# 05021002_7-Segment_Display.net
KiCad netlist of a schematic drawn in Altium Designer
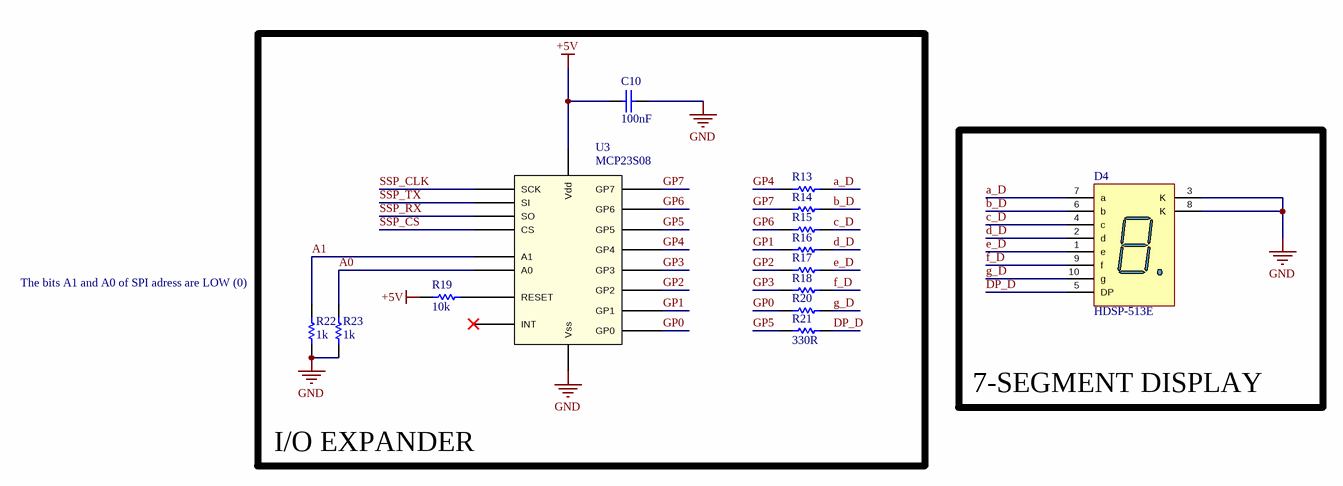
[diagram p0: 05021002_7-Segment Display.SchDoc]

(export (version "E")
  (design (tool "Eeschema 10.0.6"))
  (components
    (comp (ref "C10")
      (value "100nF")
      (footprint "CAPC2012X135N")
      (description "Generic Capacitor")
      (libsource (lib "capacitor_smd_gen") (part "capacitor_gen"))
    )
    (comp (ref "D4")
      (value "HDSP-513E")
      (footprint "HDSP-513E")
      (description "14.22 mm (0.56 inch) Single Digit General Purpose Seven Segment Display")
      (libsource (lib "IPÊ_BOARD_LIBRARY") (part "HDSP-513E"))
    )
    (comp (ref "R13")
      (value "330R")
      (footprint "0805")
      (libsource (lib "resistor_smd_gen") (part "resistor_gen"))
    )
    (comp (ref "R14")
      (value "330R")
      (footprint "0805")
      (libsource (lib "resistor_smd_gen") (part "resistor_gen"))
    )
    (comp (ref "R15")
      (value "330R")
      (footprint "0805")
      (libsource (lib "resistor_smd_gen") (part "resistor_gen"))
    )
    (comp (ref "R16")
      (value "330R")
      (footprint "0805")
      (libsource (lib "resistor_smd_gen") (part "resistor_gen"))
    )
    (comp (ref "R17")
      (value "330R")
      (footprint "0805")
      (libsource (lib "resistor_smd_gen") (part "resistor_gen"))
    )
    (comp (ref "R18")
      (value "330R")
      (footprint "0805")
      (libsource (lib "resistor_smd_gen") (part "resistor_gen"))
    )
    (comp (ref "R19")
      (value "10k")
      (footprint "0805")
      (libsource (lib "resistor_smd_gen") (part "resistor_gen"))
    )
    (comp (ref "R20")
      (value "330R")
      (footprint "0805")
      (libsource (lib "resistor_smd_gen") (part "resistor_gen"))
    )
    (comp (ref "R21")
      (value "330R")
      (footprint "0805")
      (libsource (lib "resistor_smd_gen") (part "resistor_gen"))
    )
    (comp (ref "R22")
      (value "1k")
      (footprint "0805")
      (libsource (lib "resistor_smd_gen") (part "resistor_gen"))
    )
    (comp (ref "R23")
      (value "1k")
      (footprint "0805")
      (libsource (lib "resistor_smd_gen") (part "resistor_gen"))
    )
    (comp (ref "U3")
      (value "MCP23S08")
      (footprint "SSOP20")
      (description "8-Bit I/O Expander with Serial Interface")
      (libsource (lib "IPÊ_BOARD_LIBRARY") (part "MCP23S08"))
    )
  )
  (nets
    (net (code "1") (name "+5V") (class "Default")
      (node (ref "C10") (pin "1") (pinfunction "1_1") (pintype "passive"))
      (node (ref "R19") (pin "2") (pinfunction "2_2") (pintype "passive"))
      (node (ref "U3") (pin "20") (pinfunction "Vdd_20") (pintype "passive"))
    )
    (net (code "2") (name "/A0") (class "Default")
      (node (ref "R23") (pin "2") (pinfunction "2_2") (pintype "passive"))
      (node (ref "U3") (pin "5") (pinfunction "A0_5") (pintype "passive"))
    )
    (net (code "3") (name "/A1") (class "Default")
      (node (ref "R22") (pin "2") (pinfunction "2_2") (pintype "passive"))
      (node (ref "U3") (pin "4") (pinfunction "A1_4") (pintype "passive"))
    )
    (net (code "4") (name "/DP_D") (class "Default")
      (node (ref "D4") (pin "5") (pinfunction "DP_5") (pintype "passive"))
      (node (ref "R21") (pin "2") (pinfunction "2_2") (pintype "passive"))
    )
    (net (code "5") (name "/GP0") (class "Default")
      (node (ref "R20") (pin "1") (pinfunction "1_1") (pintype "passive"))
      (node (ref "U3") (pin "12") (pinfunction "GP0_12") (pintype "passive"))
    )
    (net (code "6") (name "/GP1") (class "Default")
      (node (ref "R16") (pin "1") (pinfunction "1_1") (pintype "passive"))
      (node (ref "U3") (pin "13") (pinfunction "GP1_13") (pintype "passive"))
    )
    (net (code "7") (name "/GP2") (class "Default")
      (node (ref "R17") (pin "1") (pinfunction "1_1") (pintype "passive"))
      (node (ref "U3") (pin "14") (pinfunction "GP2_14") (pintype "passive"))
    )
    (net (code "8") (name "/GP3") (class "Default")
      (node (ref "R18") (pin "1") (pinfunction "1_1") (pintype "passive"))
      (node (ref "U3") (pin "15") (pinfunction "GP3_15") (pintype "passive"))
    )
    (net (code "9") (name "/GP4") (class "Default")
      (node (ref "R13") (pin "1") (pinfunction "1_1") (pintype "passive"))
      (node (ref "U3") (pin "16") (pinfunction "GP4_16") (pintype "passive"))
    )
    (net (code "10") (name "/GP5") (class "Default")
      (node (ref "R21") (pin "1") (pinfunction "1_1") (pintype "passive"))
      (node (ref "U3") (pin "17") (pinfunction "GP5_17") (pintype "passive"))
    )
    (net (code "11") (name "/GP6") (class "Default")
      (node (ref "R15") (pin "1") (pinfunction "1_1") (pintype "passive"))
      (node (ref "U3") (pin "18") (pinfunction "GP6_18") (pintype "passive"))
    )
    (net (code "12") (name "/GP7") (class "Default")
      (node (ref "R14") (pin "1") (pinfunction "1_1") (pintype "passive"))
      (node (ref "U3") (pin "19") (pinfunction "GP7_19") (pintype "passive"))
    )
    (net (code "13") (name "/SSP_CLK") (class "Default")
      (node (ref "U3") (pin "1") (pinfunction "SCK_1") (pintype "passive"))
    )
    (net (code "14") (name "/SSP_CS") (class "Default")
      (node (ref "U3") (pin "7") (pinfunction "CS_7") (pintype "passive"))
    )
    (net (code "15") (name "/SSP_RX") (class "Default")
      (node (ref "U3") (pin "3") (pinfunction "SO_3") (pintype "passive"))
    )
    (net (code "16") (name "/SSP_TX") (class "Default")
      (node (ref "U3") (pin "2") (pinfunction "SI_2") (pintype "passive"))
    )
    (net (code "17") (name "/a_D") (class "Default")
      (node (ref "D4") (pin "7") (pinfunction "a_7") (pintype "passive"))
      (node (ref "R13") (pin "2") (pinfunction "2_2") (pintype "passive"))
    )
    (net (code "18") (name "/b_D") (class "Default")
      (node (ref "D4") (pin "6") (pinfunction "b_6") (pintype "passive"))
      (node (ref "R14") (pin "2") (pinfunction "2_2") (pintype "passive"))
    )
    (net (code "19") (name "/c_D") (class "Default")
      (node (ref "D4") (pin "4") (pinfunction "c_4") (pintype "passive"))
      (node (ref "R15") (pin "2") (pinfunction "2_2") (pintype "passive"))
    )
    (net (code "20") (name "/d_D") (class "Default")
      (node (ref "D4") (pin "2") (pinfunction "d_2") (pintype "passive"))
      (node (ref "R16") (pin "2") (pinfunction "2_2") (pintype "passive"))
    )
    (net (code "21") (name "/e_D") (class "Default")
      (node (ref "D4") (pin "1") (pinfunction "e_1") (pintype "passive"))
      (node (ref "R17") (pin "2") (pinfunction "2_2") (pintype "passive"))
    )
    (net (code "22") (name "/f_D") (class "Default")
      (node (ref "D4") (pin "9") (pinfunction "f_9") (pintype "passive"))
      (node (ref "R18") (pin "2") (pinfunction "2_2") (pintype "passive"))
    )
    (net (code "23") (name "/g_D") (class "Default")
      (node (ref "D4") (pin "10") (pinfunction "g_10") (pintype "passive"))
      (node (ref "R20") (pin "2") (pinfunction "2_2") (pintype "passive"))
    )
    (net (code "24") (name "GND") (class "Default")
      (node (ref "C10") (pin "2") (pinfunction "2_2") (pintype "passive"))
      (node (ref "D4") (pin "3") (pinfunction "K_3") (pintype "passive"))
      (node (ref "D4") (pin "8") (pinfunction "K_8") (pintype "passive"))
      (node (ref "R22") (pin "1") (pinfunction "1_1") (pintype "passive"))
      (node (ref "R23") (pin "1") (pinfunction "1_1") (pintype "passive"))
      (node (ref "U3") (pin "9") (pinfunction "Vss_9") (pintype "passive"))
    )
    (net (code "25") (name "Net-(U3-RESET)") (class "Default")
      (node (ref "R19") (pin "1") (pinfunction "1_1") (pintype "passive"))
      (node (ref "U3") (pin "6") (pinfunction "RESET_6") (pintype "passive"))
    )
    (net (code "26") (name "unconnected-(U3-INT-Pad8)") (class "Default")
      (node (ref "U3") (pin "8") (pinfunction "INT_8") (pintype "passive+no_connect"))
    )
  )
)
